# I2c_DAC.net
KiCad netlist of a schematic drawn in EAGLE
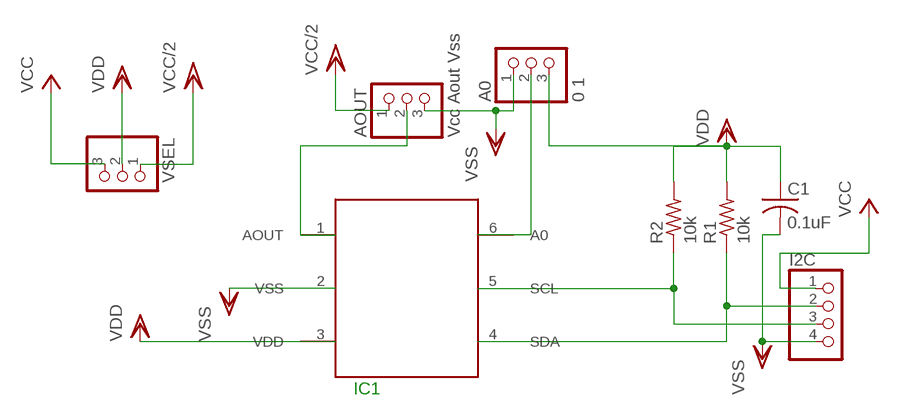
[diagram p0: schematic, sheet 1]

(export (version "E")
  (design (tool "Eeschema 10.0.6"))
  (components
    (comp (ref "A0")
      (value "0 1")
      (footprint "eagle-import:1X03")
      (libsource (lib "eagle-import") (part "PINHD-1X3"))
    )
    (comp (ref "AOUT")
      (value "Vcc Aout Vss")
      (footprint "eagle-import:1X03")
      (libsource (lib "eagle-import") (part "PINHD-1X3"))
    )
    (comp (ref "C1")
      (value "0.1uF")
      (footprint "eagle-import:C0402")
      (libsource (lib "eagle-import") (part "C-USC0402"))
    )
    (comp (ref "I2C")
      (value "PINHD-1X4")
      (footprint "eagle-import:1X04")
      (libsource (lib "eagle-import") (part "PINHD-1X4"))
    )
    (comp (ref "IC1")
      (value "MCP4725")
      (footprint "eagle-import:SOT23-6")
      (libsource (lib "eagle-import") (part "MCP4725"))
    )
    (comp (ref "R1")
      (value "10k")
      (footprint "eagle-import:R0402")
      (libsource (lib "eagle-import") (part "R-US_R0402"))
    )
    (comp (ref "R2")
      (value "10k")
      (footprint "eagle-import:R0402")
      (libsource (lib "eagle-import") (part "R-US_R0402"))
    )
    (comp (ref "VSEL")
      (value "PINHD-1X3")
      (footprint "eagle-import:1X03")
      (libsource (lib "eagle-import") (part "PINHD-1X3"))
    )
  )
  (nets
    (net (code "1") (name "Net-(IC1-A0)") (class "Default")
      (node (ref "A0") (pin "2") (pinfunction "2_2") (pintype "passive"))
      (node (ref "IC1") (pin "6") (pinfunction "A0_6") (pintype "bidirectional"))
    )
    (net (code "2") (name "Net-(IC1-AOUT)") (class "Default")
      (node (ref "AOUT") (pin "2") (pinfunction "2_2") (pintype "passive"))
      (node (ref "IC1") (pin "1") (pinfunction "AOUT_1") (pintype "bidirectional"))
    )
    (net (code "3") (name "Net-(IC1-SCL)") (class "Default")
      (node (ref "I2C") (pin "3") (pinfunction "3_3") (pintype "passive"))
      (node (ref "IC1") (pin "5") (pinfunction "SCL_5") (pintype "bidirectional"))
      (node (ref "R2") (pin "1") (pinfunction "1_1") (pintype "passive"))
    )
    (net (code "4") (name "Net-(IC1-SDA)") (class "Default")
      (node (ref "I2C") (pin "2") (pinfunction "2_2") (pintype "passive"))
      (node (ref "IC1") (pin "4") (pinfunction "SDA_4") (pintype "bidirectional"))
      (node (ref "R1") (pin "1") (pinfunction "1_1") (pintype "passive"))
    )
    (net (code "5") (name "VCC") (class "Default")
      (node (ref "I2C") (pin "1") (pinfunction "1_1") (pintype "passive"))
      (node (ref "VSEL") (pin "3") (pinfunction "3_3") (pintype "passive"))
    )
    (net (code "6") (name "VCC{slash}2") (class "Default")
      (node (ref "AOUT") (pin "1") (pinfunction "1_1") (pintype "passive"))
      (node (ref "VSEL") (pin "1") (pinfunction "1_1") (pintype "passive"))
    )
    (net (code "7") (name "VDD") (class "Default")
      (node (ref "A0") (pin "3") (pinfunction "3_3") (pintype "passive"))
      (node (ref "C1") (pin "1") (pinfunction "1_1") (pintype "passive"))
      (node (ref "IC1") (pin "3") (pinfunction "VDD_3") (pintype "bidirectional"))
      (node (ref "R1") (pin "2") (pinfunction "2_2") (pintype "passive"))
      (node (ref "R2") (pin "2") (pinfunction "2_2") (pintype "passive"))
      (node (ref "VSEL") (pin "2") (pinfunction "2_2") (pintype "passive"))
    )
    (net (code "8") (name "VSS") (class "Default")
      (node (ref "A0") (pin "1") (pinfunction "1_1") (pintype "passive"))
      (node (ref "AOUT") (pin "3") (pinfunction "3_3") (pintype "passive"))
      (node (ref "C1") (pin "2") (pinfunction "2_2") (pintype "passive"))
      (node (ref "I2C") (pin "4") (pinfunction "4_4") (pintype "passive"))
      (node (ref "IC1") (pin "2") (pinfunction "VSS_2") (pintype "bidirectional"))
    )
  )
)
